# 04_Sensor.net
KiCad netlist of a schematic drawn in Altium Designer
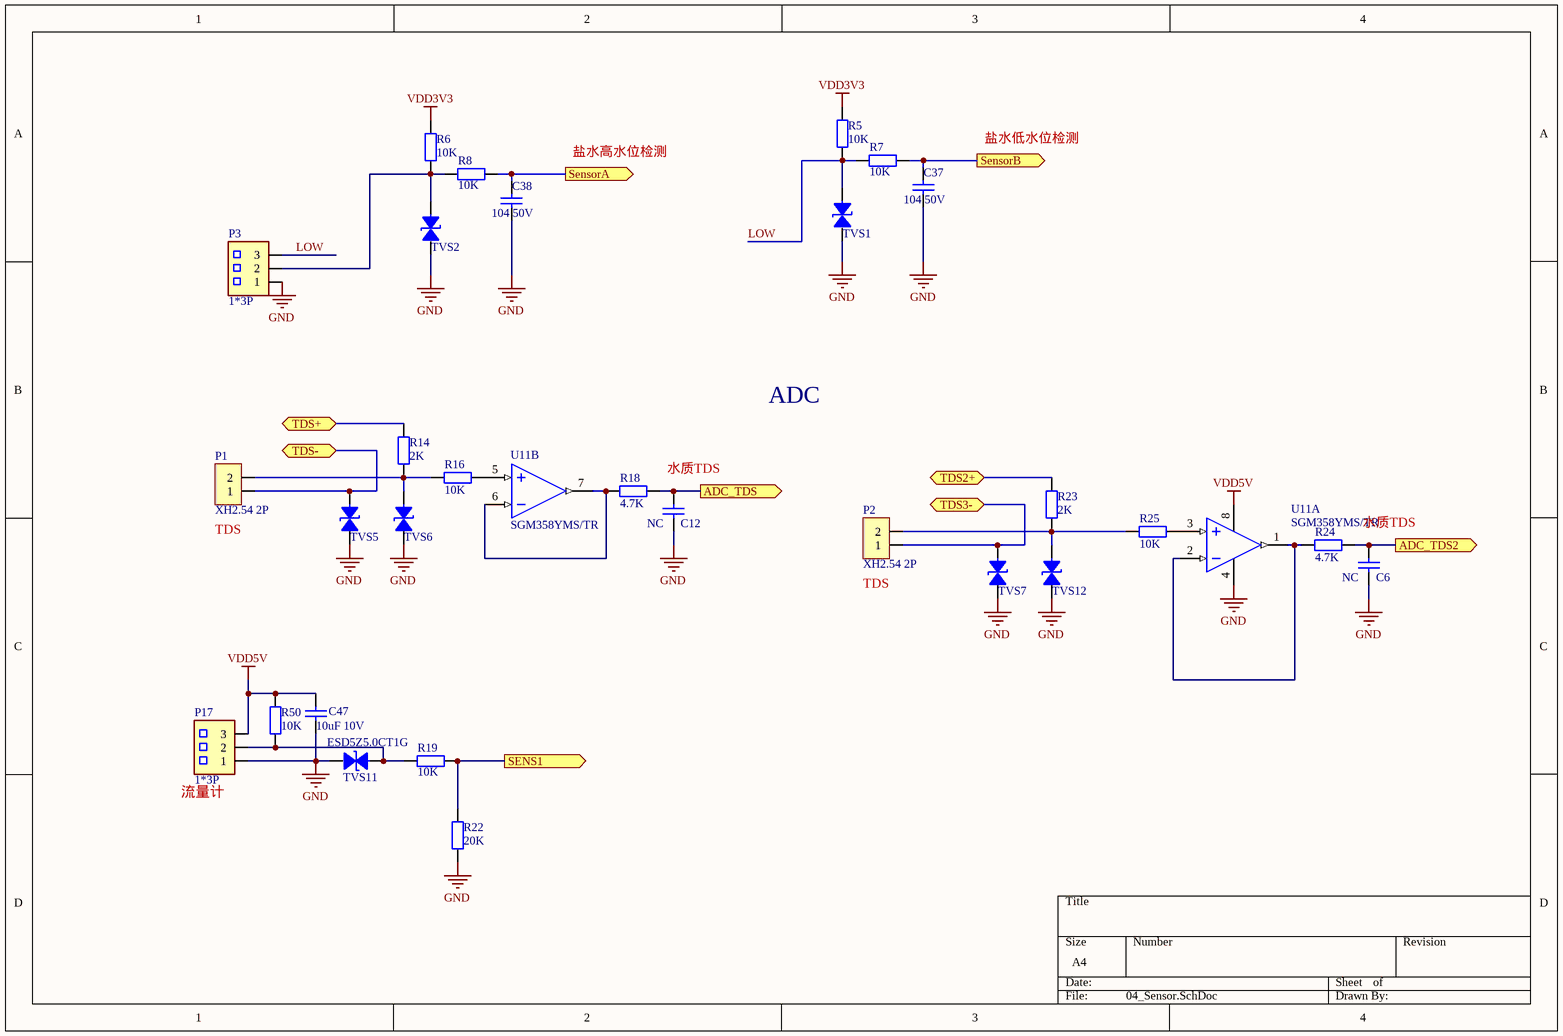
[diagram p0: 04_Sensor.SchDoc]

(export (version "E")
  (design (tool "Eeschema 10.0.6"))
  (components
    (comp (ref "C6")
      (value "NC")
      (footprint "0603C")
      (description "贴片电容 10%")
      (libsource (lib "XiaoyI") (part "CAP4"))
    )
    (comp (ref "C12")
      (value "NC")
      (footprint "SMD-0603C")
      (description "贴片电容 10%")
      (libsource (lib "XiaoyI") (part "CAP4"))
    )
    (comp (ref "C37")
      (value "104 50V")
      (footprint "SMD-0603C")
      (description "贴片电容 20%")
      (libsource (lib "XiaoyI") (part "CAP4"))
    )
    (comp (ref "C38")
      (value "104 50V")
      (footprint "SMD-0603C")
      (description "贴片电容 20%")
      (libsource (lib "XiaoyI") (part "CAP4"))
    )
    (comp (ref "C47")
      (value "10uF 10V")
      (footprint "SMD-0603C")
      (description "贴片电容 10%")
      (libsource (lib "Miscellaneous Devices LC") (part "0805 22uF (226) 20% 25V"))
    )
    (comp (ref "P1")
      (value "XH2.54 2P")
      (footprint "SIP-2A")
      (description "XH2.54 2P 直插")
      (libsource (lib "XiaoyI") (part "SIP-2"))
    )
    (comp (ref "P2")
      (value "XH2.54 2P")
      (footprint "SIP-2A")
      (description "XH2.54 2P 直插")
      (libsource (lib "XiaoyI") (part "SIP-2"))
    )
    (comp (ref "P3") (value "1*3P") (footprint "3X2MMZ") (libsource (lib "PARK-N5 V1.0") (part "HDR1*3")))
    (comp (ref "P17")
      (value "1*3P")
      (footprint "3X2.54MMZ2")
      (libsource (lib "PARK-N5 V1.0") (part "HDR1*3"))
    )
    (comp (ref "R5")
      (value "10K")
      (footprint "SMD-0603")
      (description "贴片电阻 1%")
      (libsource (lib "") (part "RES0_1"))
    )
    (comp (ref "R6")
      (value "10K")
      (footprint "SMD-0603")
      (description "贴片电阻 1%")
      (libsource (lib "") (part "RES0_1"))
    )
    (comp (ref "R7")
      (value "10K")
      (footprint "SMD-0603")
      (description "贴片电阻 1%")
      (libsource (lib "") (part "RES0_2"))
    )
    (comp (ref "R8")
      (value "10K")
      (footprint "SMD-0603")
      (description "贴片电阻 1%")
      (libsource (lib "") (part "RES0_2"))
    )
    (comp (ref "R14")
      (value "2K")
      (footprint "SMD-0603")
      (description "贴片电阻 1%")
      (libsource (lib "") (part "RES0_1"))
    )
    (comp (ref "R16")
      (value "10K")
      (footprint "SMD-0603")
      (description "贴片电阻 1%")
      (libsource (lib "") (part "RES0_2"))
    )
    (comp (ref "R18")
      (value "4.7K")
      (footprint "SMD-0603")
      (description "贴片电阻 5%")
      (libsource (lib "ABB") (part "RES0"))
    )
    (comp (ref "R19")
      (value "10K")
      (footprint "SMD-0603")
      (description "贴片电阻 5%")
      (libsource (lib "") (part "0603 10KΩ (1002) 1%_1"))
    )
    (comp (ref "R22")
      (value "20K")
      (footprint "SMD-0603")
      (description "贴片电阻 5%")
      (libsource (lib "Miscellaneous Devices LC") (part "0603 10KΩ (1002) 1%"))
    )
    (comp (ref "R23")
      (value "2K")
      (footprint "0603R")
      (description "贴片电阻 1%")
      (libsource (lib "") (part "RES0_1"))
    )
    (comp (ref "R24")
      (value "4.7K")
      (footprint "0603R")
      (description "贴片电阻 5%")
      (libsource (lib "ABB") (part "RES0"))
    )
    (comp (ref "R25")
      (value "10K")
      (footprint "SMD-0603")
      (description "贴片电阻 1%")
      (libsource (lib "") (part "RES0_2"))
    )
    (comp (ref "R50")
      (value "10K")
      (footprint "SMD-0603")
      (description "贴片电阻 5%")
      (libsource (lib "") (part "0603 10KΩ (1002) 1%_2"))
    )
    (comp (ref "TVS1")
      (value "ESD5Z5.0CT1G")
      (footprint "SOD-523")
      (description "TVS")
      (libsource (lib "XiaoyI") (part "TVS-1"))
    )
    (comp (ref "TVS2")
      (value "ESD5Z5.0CT1G")
      (footprint "SOD-523")
      (description "TVS")
      (libsource (lib "XiaoyI") (part "TVS-1"))
    )
    (comp (ref "TVS5")
      (value "ESD5Z5.0CT1G")
      (footprint "SOD-523")
      (description "TVS")
      (libsource (lib "XiaoyI") (part "TVS-1"))
    )
    (comp (ref "TVS6")
      (value "ESD5Z5.0CT1G")
      (footprint "SOD-523")
      (description "TVS")
      (libsource (lib "XiaoyI") (part "TVS-1"))
    )
    (comp (ref "TVS7")
      (value "ESD5Z5.0CT1G")
      (footprint "SOD-523")
      (description "TVS")
      (libsource (lib "XiaoyI") (part "TVS-1"))
    )
    (comp (ref "TVS11")
      (value "ESD5Z5.0CT1G")
      (footprint "SOD-523")
      (description "TVS 5.0V")
      (libsource (lib "XiaoyI") (part "TVS-1"))
    )
    (comp (ref "TVS12")
      (value "ESD5Z5.0CT1G")
      (footprint "SOD-523")
      (description "TVS")
      (libsource (lib "XiaoyI") (part "TVS-1"))
    )
    (comp (ref "U11")
      (value "SGM358YMS/TR")
      (footprint "MSOP-8")
      (description "运放")
      (libsource (lib "XiaoyI") (part "LM358"))
    )
  )
  (nets
    (net (code "1") (name "/ADC_TDS") (class "Default")
      (node (ref "C12") (pin "2") (pinfunction "2_2") (pintype "passive"))
      (node (ref "R18") (pin "1") (pinfunction "1_1") (pintype "passive"))
    )
    (net (code "2") (name "/ADC_TDS2") (class "Default")
      (node (ref "C6") (pin "2") (pinfunction "2_2") (pintype "passive"))
      (node (ref "R24") (pin "1") (pinfunction "1_1") (pintype "passive"))
    )
    (net (code "3") (name "/LOW") (class "Default")
      (node (ref "P3") (pin "3") (pinfunction "3_3") (pintype "passive"))
      (node (ref "R5") (pin "2") (pinfunction "2_2") (pintype "passive"))
      (node (ref "R7") (pin "1") (pinfunction "1_1") (pintype "passive"))
      (node (ref "TVS1") (pin "2") (pinfunction "B_2") (pintype "passive"))
    )
    (net (code "4") (name "/SENS1") (class "Default")
      (node (ref "R19") (pin "2") (pinfunction "2_2") (pintype "passive"))
      (node (ref "R22") (pin "2") (pinfunction "2_2") (pintype "passive"))
    )
    (net (code "5") (name "/SensorA") (class "Default")
      (node (ref "C38") (pin "2") (pinfunction "2_2") (pintype "passive"))
      (node (ref "R8") (pin "2") (pinfunction "2_2") (pintype "passive"))
    )
    (net (code "6") (name "/SensorB") (class "Default")
      (node (ref "C37") (pin "2") (pinfunction "2_2") (pintype "passive"))
      (node (ref "R7") (pin "2") (pinfunction "2_2") (pintype "passive"))
    )
    (net (code "7") (name "/TDS+") (class "Default")
      (node (ref "R14") (pin "1") (pinfunction "1_1") (pintype "passive"))
    )
    (net (code "8") (name "/TDS-") (class "Default")
      (node (ref "P1") (pin "1") (pinfunction "1_1") (pintype "passive"))
      (node (ref "TVS5") (pin "2") (pinfunction "B_2") (pintype "passive"))
    )
    (net (code "9") (name "/TDS2+") (class "Default")
      (node (ref "R23") (pin "1") (pinfunction "1_1") (pintype "passive"))
    )
    (net (code "10") (name "/TDS3-") (class "Default")
      (node (ref "P2") (pin "1") (pinfunction "1_1") (pintype "passive"))
      (node (ref "TVS7") (pin "2") (pinfunction "B_2") (pintype "passive"))
    )
    (net (code "11") (name "GND") (class "Default")
      (node (ref "C12") (pin "1") (pinfunction "1_1") (pintype "passive"))
      (node (ref "C37") (pin "1") (pinfunction "1_1") (pintype "passive"))
      (node (ref "C38") (pin "1") (pinfunction "1_1") (pintype "passive"))
      (node (ref "C47") (pin "1") (pinfunction "1_1") (pintype "passive"))
      (node (ref "C6") (pin "1") (pinfunction "1_1") (pintype "passive"))
      (node (ref "P17") (pin "1") (pinfunction "1_1") (pintype "passive"))
      (node (ref "P3") (pin "1") (pinfunction "1_1") (pintype "passive"))
      (node (ref "R22") (pin "1") (pinfunction "1_1") (pintype "passive"))
      (node (ref "TVS1") (pin "1") (pinfunction "A_1") (pintype "passive"))
      (node (ref "TVS11") (pin "1") (pinfunction "A_1") (pintype "passive"))
      (node (ref "TVS12") (pin "1") (pinfunction "A_1") (pintype "passive"))
      (node (ref "TVS2") (pin "1") (pinfunction "A_1") (pintype "passive"))
      (node (ref "TVS5") (pin "1") (pinfunction "A_1") (pintype "passive"))
      (node (ref "TVS6") (pin "1") (pinfunction "A_1") (pintype "passive"))
      (node (ref "TVS7") (pin "1") (pinfunction "A_1") (pintype "passive"))
      (node (ref "U11") (pin "4") (pinfunction "V-_4") (pintype "power_in"))
    )
    (net (code "12") (name "Net-(TVS2-B)") (class "Default")
      (node (ref "P3") (pin "2") (pinfunction "2_2") (pintype "passive"))
      (node (ref "R6") (pin "2") (pinfunction "2_2") (pintype "passive"))
      (node (ref "R8") (pin "1") (pinfunction "1_1") (pintype "passive"))
      (node (ref "TVS2") (pin "2") (pinfunction "B_2") (pintype "passive"))
    )
    (net (code "13") (name "Net-(TVS6-B)") (class "Default")
      (node (ref "P1") (pin "2") (pinfunction "2_2") (pintype "passive"))
      (node (ref "R14") (pin "2") (pinfunction "2_2") (pintype "passive"))
      (node (ref "R16") (pin "1") (pinfunction "1_1") (pintype "passive"))
      (node (ref "TVS6") (pin "2") (pinfunction "B_2") (pintype "passive"))
    )
    (net (code "14") (name "Net-(TVS11-B)") (class "Default")
      (node (ref "P17") (pin "2") (pinfunction "2_2") (pintype "passive"))
      (node (ref "R19") (pin "1") (pinfunction "1_1") (pintype "passive"))
      (node (ref "R50") (pin "2") (pinfunction "2_2") (pintype "passive"))
      (node (ref "TVS11") (pin "2") (pinfunction "B_2") (pintype "passive"))
    )
    (net (code "15") (name "Net-(TVS12-B)") (class "Default")
      (node (ref "P2") (pin "2") (pinfunction "2_2") (pintype "passive"))
      (node (ref "R23") (pin "2") (pinfunction "2_2") (pintype "passive"))
      (node (ref "R25") (pin "1") (pinfunction "1_1") (pintype "passive"))
      (node (ref "TVS12") (pin "2") (pinfunction "B_2") (pintype "passive"))
    )
    (net (code "16") (name "Net-(U11A-IN1+)") (class "Default")
      (node (ref "R25") (pin "2") (pinfunction "2_2") (pintype "passive"))
      (node (ref "U11") (pin "3") (pinfunction "IN1+_3") (pintype "input"))
    )
    (net (code "17") (name "Net-(U11A-IN1-)") (class "Default")
      (node (ref "R24") (pin "2") (pinfunction "2_2") (pintype "passive"))
      (node (ref "U11") (pin "1") (pinfunction "OUT1_1") (pintype "output"))
      (node (ref "U11") (pin "2") (pinfunction "IN1-_2") (pintype "input"))
    )
    (net (code "18") (name "Net-(U11B-IN2+)") (class "Default")
      (node (ref "R16") (pin "2") (pinfunction "2_2") (pintype "passive"))
      (node (ref "U11") (pin "5") (pinfunction "IN2+_5") (pintype "input"))
    )
    (net (code "19") (name "Net-(U11B-IN2-)") (class "Default")
      (node (ref "R18") (pin "2") (pinfunction "2_2") (pintype "passive"))
      (node (ref "U11") (pin "6") (pinfunction "IN2-_6") (pintype "input"))
      (node (ref "U11") (pin "7") (pinfunction "OUT2_7") (pintype "output"))
    )
    (net (code "20") (name "VDD3V3") (class "Default")
      (node (ref "R5") (pin "1") (pinfunction "1_1") (pintype "passive"))
      (node (ref "R6") (pin "1") (pinfunction "1_1") (pintype "passive"))
    )
    (net (code "21") (name "VDD5V") (class "Default")
      (node (ref "C47") (pin "2") (pinfunction "2_2") (pintype "passive"))
      (node (ref "P17") (pin "3") (pinfunction "3_3") (pintype "passive"))
      (node (ref "R50") (pin "1") (pinfunction "1_1") (pintype "passive"))
      (node (ref "U11") (pin "8") (pinfunction "V+_8") (pintype "power_in"))
    )
  )
)
